# Sheet1.net
KiCad netlist of a schematic drawn in Altium Designer
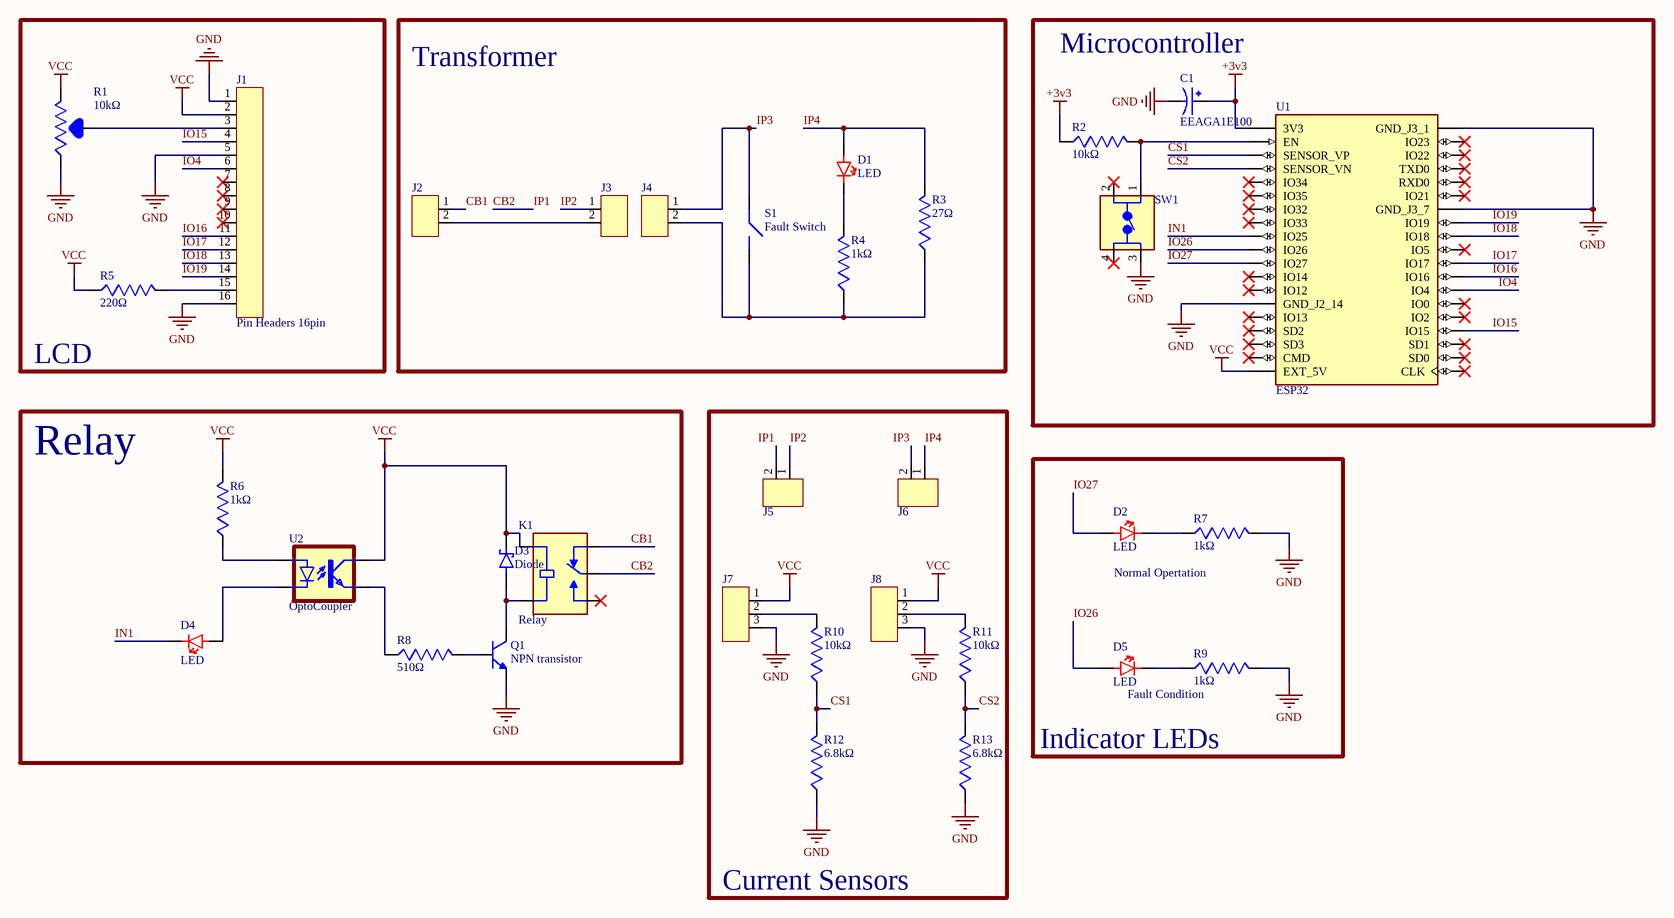
[diagram p0: Sheet1.SchDoc]

(export (version "E")
  (design (tool "Eeschema 10.0.6"))
  (components
    (comp (ref "C1")
      (value "EEAGA1E100")
      (footprint "CAPPRD150W45D400H700")
      (description "CAP ALUM 10UF 20% 25V RADIAL")
      (fields (field (name "MF") "Panasonic") (field (name "MP") "EEA-GA1E100"))
      (libsource (lib "EEAGA1E100 (1)") (part "EEAGA1E100"))
    )
    (comp (ref "D1") (value "LED") (footprint "LED") (libsource (lib "Schlib2") (part "LED")))
    (comp (ref "D2") (value "LED") (footprint "LED") (libsource (lib "Schlib2") (part "LED")))
    (comp (ref "D3") (value "Diode") (footprint "Diode") (libsource (lib "Schlib2") (part "Diode")))
    (comp (ref "D4") (value "LED") (footprint "LED") (libsource (lib "Schlib2") (part "LED")))
    (comp (ref "D5") (value "LED") (footprint "LED") (libsource (lib "Schlib2") (part "LED")))
    (comp (ref "J1")
      (value "Pin Headers 16pin")
      (footprint "16 pin header")
      (libsource (lib "Schlib2") (part "Pin Headers 16pin"))
    )
    (comp (ref "J2")
      (value "~")
      (footprint "Barrier terminal")
      (libsource (lib "Schlib2") (part "Terminal Barrier"))
    )
    (comp (ref "J3")
      (value "~")
      (footprint "Barrier terminal")
      (libsource (lib "") (part "Terminal Barrier_1"))
    )
    (comp (ref "J4")
      (value "~")
      (footprint "Barrier terminal")
      (libsource (lib "Schlib2") (part "Terminal Barrier"))
    )
    (comp (ref "J5")
      (value "~")
      (footprint "2 Pin header")
      (libsource (lib "Schlib2") (part "Pin Headers 2pins right angled"))
    )
    (comp (ref "J6")
      (value "~")
      (footprint "2 Pin header")
      (libsource (lib "Schlib2") (part "Pin Headers 2pins right angled"))
    )
    (comp (ref "J7")
      (value "~")
      (footprint "CURRENT SENSOR")
      (libsource (lib "Schlib2") (part "Pin Headers 3pins"))
    )
    (comp (ref "J8")
      (value "~")
      (footprint "CURRENT SENSOR")
      (libsource (lib "Schlib2") (part "Pin Headers 3pins"))
    )
    (comp (ref "K1") (value "Relay") (footprint "Relay") (libsource (lib "Schlib2") (part "Relay")))
    (comp (ref "Q1")
      (value "NPN transistor")
      (footprint "2N2222")
      (libsource (lib "Schlib2") (part "NPN transistor"))
    )
    (comp (ref "R1")
      (value "10kΩ")
      (footprint "Pot_resistor")
      (libsource (lib "Schlib2") (part "potentiometer"))
    )
    (comp (ref "R2") (value "10kΩ") (footprint "resistor") (libsource (lib "Schlib2") (part "Resistor")))
    (comp (ref "R3")
      (value "27Ω")
      (footprint "Power res")
      (libsource (lib "Schlib2") (part "Power Resistor"))
    )
    (comp (ref "R4") (value "1kΩ") (footprint "resistor") (libsource (lib "Schlib2") (part "Resistor")))
    (comp (ref "R5") (value "220Ω") (footprint "resistor") (libsource (lib "Schlib2") (part "Resistor")))
    (comp (ref "R6") (value "1kΩ") (footprint "resistor") (libsource (lib "Schlib2") (part "Resistor")))
    (comp (ref "R7") (value "1kΩ") (footprint "resistor") (libsource (lib "Schlib2") (part "Resistor")))
    (comp (ref "R8") (value "510Ω") (footprint "resistor") (libsource (lib "Schlib2") (part "Resistor")))
    (comp (ref "R9") (value "1kΩ") (footprint "resistor") (libsource (lib "Schlib2") (part "Resistor")))
    (comp (ref "R10") (value "10kΩ") (footprint "resistor") (libsource (lib "Schlib2") (part "Resistor")))
    (comp (ref "R11") (value "10kΩ") (footprint "resistor") (libsource (lib "Schlib2") (part "Resistor")))
    (comp (ref "R12") (value "6.8kΩ") (footprint "resistor") (libsource (lib "Schlib2") (part "Resistor")))
    (comp (ref "R13") (value "6.8kΩ") (footprint "resistor") (libsource (lib "Schlib2") (part "Resistor")))
    (comp (ref "S1")
      (value "Fault Switch")
      (footprint "Fault switch")
      (libsource (lib "Schlib2") (part "Fault Switch"))
    )
    (comp (ref "SW1")
      (value "Tact_Switch")
      (footprint "Tact_Switch")
      (libsource (lib "Schlib2") (part "Tact_Switch"))
    )
    (comp (ref "U1") (value "ESP32") (footprint "ESP32") (libsource (lib "Schlib2") (part "ESP32")))
    (comp (ref "U2")
      (value "OptoCoupler")
      (footprint "opto")
      (libsource (lib "Schlib2") (part "OptoCoupler"))
    )
  )
  (nets
    (net (code "1") (name "+3v3") (class "Default")
      (node (ref "C1") (pin "P") (pinfunction "P_P") (pintype "passive"))
      (node (ref "R2") (pin "1") (pinfunction "1_1") (pintype "passive"))
      (node (ref "U1") (pin "J2_1") (pinfunction "3V3_J2_1") (pintype "power_in"))
    )
    (net (code "2") (name "/CB1") (class "Default")
      (node (ref "J2") (pin "1") (pintype "passive"))
      (node (ref "K1") (pin "NC") (pinfunction "NC_NC") (pintype "passive"))
    )
    (net (code "3") (name "/CB2") (class "Default")
      (node (ref "J5") (pin "2") (pintype "passive"))
      (node (ref "K1") (pin "COM") (pinfunction "COM_COM") (pintype "passive"))
    )
    (net (code "4") (name "/CS1") (class "Default")
      (node (ref "R10") (pin "1") (pinfunction "1_1") (pintype "passive"))
      (node (ref "R12") (pin "2") (pinfunction "2_2") (pintype "passive"))
      (node (ref "U1") (pin "J2_3") (pinfunction "SENSOR_VP_J2_3") (pintype "bidirectional"))
    )
    (net (code "5") (name "/CS2") (class "Default")
      (node (ref "R11") (pin "1") (pinfunction "1_1") (pintype "passive"))
      (node (ref "R13") (pin "2") (pinfunction "2_2") (pintype "passive"))
      (node (ref "U1") (pin "J2_4") (pinfunction "SENSOR_VN_J2_4") (pintype "bidirectional"))
    )
    (net (code "6") (name "/IN1") (class "Default")
      (node (ref "D4") (pin "2") (pinfunction "K_2") (pintype "passive"))
      (node (ref "U1") (pin "J2_9") (pinfunction "IO25_J2_9") (pintype "bidirectional"))
    )
    (net (code "7") (name "/IO4") (class "Default")
      (node (ref "J1") (pin "6") (pintype "passive"))
      (node (ref "U1") (pin "J3_13") (pinfunction "IO4_J3_13") (pintype "bidirectional"))
    )
    (net (code "8") (name "/IO15") (class "Default")
      (node (ref "J1") (pin "4") (pintype "passive"))
      (node (ref "U1") (pin "J3_16") (pinfunction "IO15_J3_16") (pintype "bidirectional"))
    )
    (net (code "9") (name "/IO16") (class "Default")
      (node (ref "J1") (pin "11") (pintype "passive"))
      (node (ref "U1") (pin "J3_12") (pinfunction "IO16_J3_12") (pintype "bidirectional"))
    )
    (net (code "10") (name "/IO17") (class "Default")
      (node (ref "J1") (pin "12") (pintype "passive"))
      (node (ref "U1") (pin "J3_11") (pinfunction "IO17_J3_11") (pintype "bidirectional"))
    )
    (net (code "11") (name "/IO18") (class "Default")
      (node (ref "J1") (pin "13") (pintype "passive"))
      (node (ref "U1") (pin "J3_9") (pinfunction "IO18_J3_9") (pintype "bidirectional"))
    )
    (net (code "12") (name "/IO19") (class "Default")
      (node (ref "J1") (pin "14") (pintype "passive"))
      (node (ref "U1") (pin "J3_8") (pinfunction "IO19_J3_8") (pintype "bidirectional"))
    )
    (net (code "13") (name "/IO26") (class "Default")
      (node (ref "D5") (pin "1") (pinfunction "A_1") (pintype "passive"))
      (node (ref "U1") (pin "J2_10") (pinfunction "IO26_J2_10") (pintype "bidirectional"))
    )
    (net (code "14") (name "/IO27") (class "Default")
      (node (ref "D2") (pin "1") (pinfunction "A_1") (pintype "passive"))
      (node (ref "U1") (pin "J2_11") (pinfunction "IO27_J2_11") (pintype "bidirectional"))
    )
    (net (code "15") (name "/IP2") (class "Default")
      (node (ref "J3") (pin "1") (pintype "passive"))
      (node (ref "J5") (pin "1") (pintype "passive"))
    )
    (net (code "16") (name "/IP3") (class "Default")
      (node (ref "J4") (pin "1") (pintype "passive"))
      (node (ref "J6") (pin "2") (pintype "passive"))
      (node (ref "S1") (pin "1") (pinfunction "1_1") (pintype "passive"))
    )
    (net (code "17") (name "/IP4") (class "Default")
      (node (ref "D1") (pin "1") (pinfunction "A_1") (pintype "passive"))
      (node (ref "J6") (pin "1") (pintype "passive"))
      (node (ref "R3") (pin "2") (pinfunction "2_2") (pintype "passive"))
    )
    (net (code "18") (name "GND") (class "Default")
      (node (ref "C1") (pin "N") (pinfunction "N_N") (pintype "passive"))
      (node (ref "J1") (pin "1") (pintype "passive"))
      (node (ref "J1") (pin "16") (pintype "passive"))
      (node (ref "J1") (pin "5") (pintype "passive"))
      (node (ref "J7") (pin "3") (pintype "passive"))
      (node (ref "J8") (pin "3") (pintype "passive"))
      (node (ref "Q1") (pin "1") (pinfunction "E_1") (pintype "passive"))
      (node (ref "R1") (pin "1") (pinfunction "1_1") (pintype "passive"))
      (node (ref "R12") (pin "1") (pinfunction "1_1") (pintype "passive"))
      (node (ref "R13") (pin "1") (pinfunction "1_1") (pintype "passive"))
      (node (ref "R7") (pin "2") (pinfunction "2_2") (pintype "passive"))
      (node (ref "R9") (pin "2") (pinfunction "2_2") (pintype "passive"))
      (node (ref "SW1") (pin "3") (pinfunction "3_3") (pintype "passive"))
      (node (ref "U1") (pin "J2_14") (pinfunction "GND_J2_14_J2_14") (pintype "power_in"))
      (node (ref "U1") (pin "J3_1") (pinfunction "GND_J3_1_J3_1") (pintype "power_in"))
      (node (ref "U1") (pin "J3_7") (pinfunction "GND_J3_7_J3_7") (pintype "power_in"))
    )
    (net (code "19") (name "Net-(D1-K)") (class "Default")
      (node (ref "D1") (pin "2") (pinfunction "K_2") (pintype "passive"))
      (node (ref "R4") (pin "2") (pinfunction "2_2") (pintype "passive"))
    )
    (net (code "20") (name "Net-(D2-K)") (class "Default")
      (node (ref "D2") (pin "2") (pinfunction "K_2") (pintype "passive"))
      (node (ref "R7") (pin "1") (pinfunction "1_1") (pintype "passive"))
    )
    (net (code "21") (name "Net-(D3-A)") (class "Default")
      (node (ref "D3") (pin "2") (pinfunction "A_2") (pintype "passive"))
      (node (ref "K1") (pin "COIL2") (pinfunction "COIL2_COIL2") (pintype "passive"))
      (node (ref "Q1") (pin "3") (pinfunction "C_3") (pintype "passive"))
    )
    (net (code "22") (name "Net-(D4-A)") (class "Default")
      (node (ref "D4") (pin "1") (pinfunction "A_1") (pintype "passive"))
      (node (ref "U2") (pin "2") (pinfunction "C_2") (pintype "passive"))
    )
    (net (code "23") (name "Net-(D5-K)") (class "Default")
      (node (ref "D5") (pin "2") (pinfunction "K_2") (pintype "passive"))
      (node (ref "R9") (pin "1") (pinfunction "1_1") (pintype "passive"))
    )
    (net (code "24") (name "Net-(J1-Pad3)") (class "Default")
      (node (ref "J1") (pin "3") (pintype "passive"))
      (node (ref "R1") (pin "3") (pinfunction "3_3") (pintype "passive"))
    )
    (net (code "25") (name "Net-(J1-Pad15)") (class "Default")
      (node (ref "J1") (pin "15") (pintype "passive"))
      (node (ref "R5") (pin "2") (pinfunction "2_2") (pintype "passive"))
    )
    (net (code "26") (name "Net-(J2-Pad2)") (class "Default")
      (node (ref "J2") (pin "2") (pintype "passive"))
      (node (ref "J3") (pin "2") (pintype "passive"))
    )
    (net (code "27") (name "Net-(J4-Pad2)") (class "Default")
      (node (ref "J4") (pin "2") (pintype "passive"))
      (node (ref "R3") (pin "1") (pinfunction "1_1") (pintype "passive"))
      (node (ref "R4") (pin "1") (pinfunction "1_1") (pintype "passive"))
      (node (ref "S1") (pin "2") (pinfunction "2_2") (pintype "passive"))
    )
    (net (code "28") (name "Net-(J7-Pad2)") (class "Default")
      (node (ref "J7") (pin "2") (pintype "passive"))
      (node (ref "R10") (pin "2") (pinfunction "2_2") (pintype "passive"))
    )
    (net (code "29") (name "Net-(J8-Pad2)") (class "Default")
      (node (ref "J8") (pin "2") (pintype "passive"))
      (node (ref "R11") (pin "2") (pinfunction "2_2") (pintype "passive"))
    )
    (net (code "30") (name "Net-(Q1-B)") (class "Default")
      (node (ref "Q1") (pin "2") (pinfunction "B_2") (pintype "passive"))
      (node (ref "R8") (pin "2") (pinfunction "2_2") (pintype "passive"))
    )
    (net (code "31") (name "Net-(U1-EN)") (class "Default")
      (node (ref "R2") (pin "2") (pinfunction "2_2") (pintype "passive"))
      (node (ref "SW1") (pin "1") (pinfunction "1_1") (pintype "passive"))
      (node (ref "U1") (pin "J2_2") (pinfunction "EN_J2_2") (pintype "input"))
    )
    (net (code "32") (name "Net-(U2-A)") (class "Default")
      (node (ref "R6") (pin "1") (pinfunction "1_1") (pintype "passive"))
      (node (ref "U2") (pin "1") (pinfunction "A_1") (pintype "passive"))
    )
    (net (code "33") (name "Net-(U2-EMIT)") (class "Default")
      (node (ref "R8") (pin "1") (pinfunction "1_1") (pintype "passive"))
      (node (ref "U2") (pin "3") (pinfunction "EMIT_3") (pintype "passive"))
    )
    (net (code "34") (name "VCC") (class "Default")
      (node (ref "D3") (pin "1") (pinfunction "K_1") (pintype "passive"))
      (node (ref "J1") (pin "2") (pintype "passive"))
      (node (ref "J7") (pin "1") (pintype "passive"))
      (node (ref "J8") (pin "1") (pintype "passive"))
      (node (ref "K1") (pin "COIL1") (pinfunction "COIL1_COIL1") (pintype "passive"))
      (node (ref "R1") (pin "2") (pinfunction "2_2") (pintype "passive"))
      (node (ref "R5") (pin "1") (pinfunction "1_1") (pintype "passive"))
      (node (ref "R6") (pin "2") (pinfunction "2_2") (pintype "passive"))
      (node (ref "U1") (pin "J2_19") (pinfunction "EXT_5V_J2_19") (pintype "power_in"))
      (node (ref "U2") (pin "4") (pinfunction "COL_4") (pintype "passive"))
    )
    (net (code "35") (name "unconnected-(J1-Pad7)") (class "Default")
      (node (ref "J1") (pin "7") (pintype "passive+no_connect"))
    )
    (net (code "36") (name "unconnected-(J1-Pad8)") (class "Default")
      (node (ref "J1") (pin "8") (pintype "passive+no_connect"))
    )
    (net (code "37") (name "unconnected-(J1-Pad9)") (class "Default")
      (node (ref "J1") (pin "9") (pintype "passive+no_connect"))
    )
    (net (code "38") (name "unconnected-(J1-Pad10)") (class "Default")
      (node (ref "J1") (pin "10") (pintype "passive+no_connect"))
    )
    (net (code "39") (name "unconnected-(K1-PadNO)") (class "Default")
      (node (ref "K1") (pin "NO") (pinfunction "NO_NO") (pintype "passive+no_connect"))
    )
    (net (code "40") (name "unconnected-(SW1-Pad2)") (class "Default")
      (node (ref "SW1") (pin "2") (pinfunction "2_2") (pintype "passive+no_connect"))
    )
    (net (code "41") (name "unconnected-(SW1-Pad4)") (class "Default")
      (node (ref "SW1") (pin "4") (pinfunction "4_4") (pintype "passive+no_connect"))
    )
    (net (code "42") (name "unconnected-(U1-CLK-PadJ3_19)") (class "Default")
      (node (ref "U1") (pin "J3_19") (pinfunction "CLK_J3_19") (pintype "bidirectional+no_connect"))
    )
    (net (code "43") (name "unconnected-(U1-CMD-PadJ2_18)") (class "Default")
      (node (ref "U1") (pin "J2_18") (pinfunction "CMD_J2_18") (pintype "bidirectional+no_connect"))
    )
    (net (code "44") (name "unconnected-(U1-IO0-PadJ3_14)") (class "Default")
      (node (ref "U1") (pin "J3_14") (pinfunction "IO0_J3_14") (pintype "bidirectional+no_connect"))
    )
    (net (code "45") (name "unconnected-(U1-IO2-PadJ3_15)") (class "Default")
      (node (ref "U1") (pin "J3_15") (pinfunction "IO2_J3_15") (pintype "bidirectional+no_connect"))
    )
    (net (code "46") (name "unconnected-(U1-IO5-PadJ3_10)") (class "Default")
      (node (ref "U1") (pin "J3_10") (pinfunction "IO5_J3_10") (pintype "bidirectional+no_connect"))
    )
    (net (code "47") (name "unconnected-(U1-IO12-PadJ2_13)") (class "Default")
      (node (ref "U1") (pin "J2_13") (pinfunction "IO12_J2_13") (pintype "bidirectional+no_connect"))
    )
    (net (code "48") (name "unconnected-(U1-IO13-PadJ2_15)") (class "Default")
      (node (ref "U1") (pin "J2_15") (pinfunction "IO13_J2_15") (pintype "bidirectional+no_connect"))
    )
    (net (code "49") (name "unconnected-(U1-IO14-PadJ2_12)") (class "Default")
      (node (ref "U1") (pin "J2_12") (pinfunction "IO14_J2_12") (pintype "bidirectional+no_connect"))
    )
    (net (code "50") (name "unconnected-(U1-IO21-PadJ3_6)") (class "Default")
      (node (ref "U1") (pin "J3_6") (pinfunction "IO21_J3_6") (pintype "bidirectional+no_connect"))
    )
    (net (code "51") (name "unconnected-(U1-IO22-PadJ3_3)") (class "Default")
      (node (ref "U1") (pin "J3_3") (pinfunction "IO22_J3_3") (pintype "bidirectional+no_connect"))
    )
    (net (code "52") (name "unconnected-(U1-IO23-PadJ3_2)") (class "Default")
      (node (ref "U1") (pin "J3_2") (pinfunction "IO23_J3_2") (pintype "bidirectional+no_connect"))
    )
    (net (code "53") (name "unconnected-(U1-IO32-PadJ2_7)") (class "Default")
      (node (ref "U1") (pin "J2_7") (pinfunction "IO32_J2_7") (pintype "bidirectional+no_connect"))
    )
    (net (code "54") (name "unconnected-(U1-IO33-PadJ2_8)") (class "Default")
      (node (ref "U1") (pin "J2_8") (pinfunction "IO33_J2_8") (pintype "bidirectional+no_connect"))
    )
    (net (code "55") (name "unconnected-(U1-IO34-PadJ2_5)") (class "Default")
      (node (ref "U1") (pin "J2_5") (pinfunction "IO34_J2_5") (pintype "bidirectional+no_connect"))
    )
    (net (code "56") (name "unconnected-(U1-IO35-PadJ2_6)") (class "Default")
      (node (ref "U1") (pin "J2_6") (pinfunction "IO35_J2_6") (pintype "bidirectional+no_connect"))
    )
    (net (code "57") (name "unconnected-(U1-RXD0-PadJ3_5)") (class "Default")
      (node (ref "U1") (pin "J3_5") (pinfunction "RXD0_J3_5") (pintype "bidirectional+no_connect"))
    )
    (net (code "58") (name "unconnected-(U1-SD0-PadJ3_18)") (class "Default")
      (node (ref "U1") (pin "J3_18") (pinfunction "SD0_J3_18") (pintype "bidirectional+no_connect"))
    )
    (net (code "59") (name "unconnected-(U1-SD1-PadJ3_17)") (class "Default")
      (node (ref "U1") (pin "J3_17") (pinfunction "SD1_J3_17") (pintype "bidirectional+no_connect"))
    )
    (net (code "60") (name "unconnected-(U1-SD2-PadJ2_16)") (class "Default")
      (node (ref "U1") (pin "J2_16") (pinfunction "SD2_J2_16") (pintype "bidirectional+no_connect"))
    )
    (net (code "61") (name "unconnected-(U1-SD3-PadJ2_17)") (class "Default")
      (node (ref "U1") (pin "J2_17") (pinfunction "SD3_J2_17") (pintype "bidirectional+no_connect"))
    )
    (net (code "62") (name "unconnected-(U1-TXD0-PadJ3_4)") (class "Default")
      (node (ref "U1") (pin "J3_4") (pinfunction "TXD0_J3_4") (pintype "bidirectional+no_connect"))
    )
  )
)
